# power.net
KiCad netlist of a schematic drawn in Altium Designer
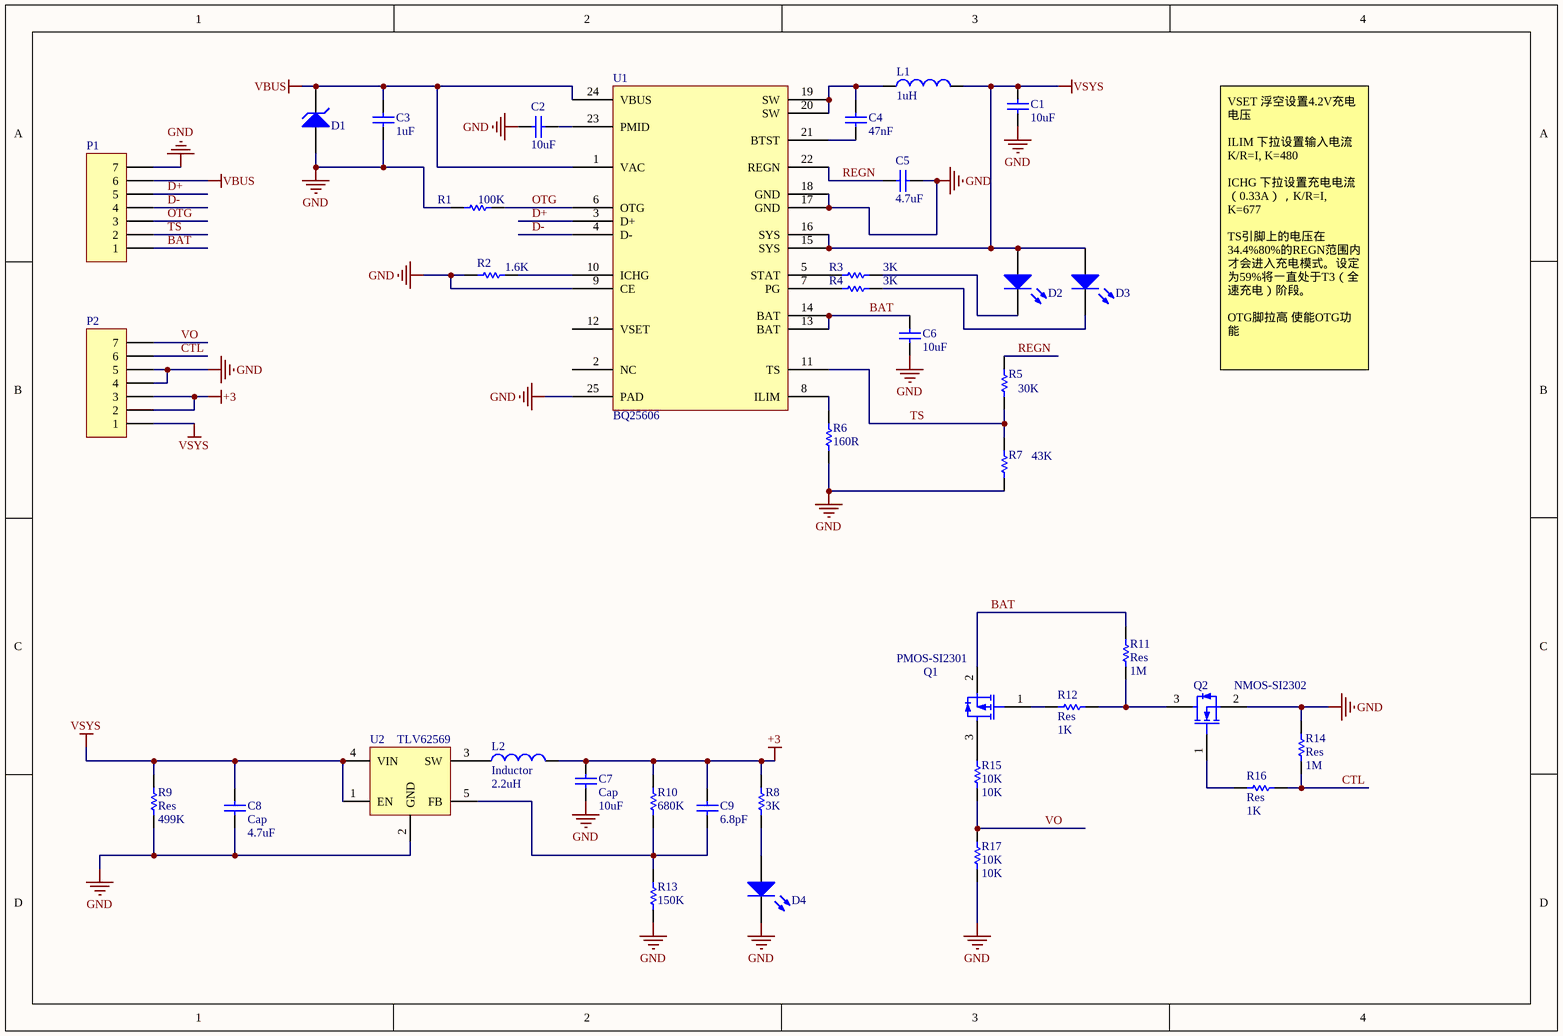
[diagram p0: power.SchDoc]

(export (version "E")
  (design (tool "Eeschema 10.0.6"))
  (components
    (comp (ref "C1")
      (value "10uF")
      (footprint "6-0805_L")
      (description "Capacitor")
      (fields (field (name "PUBLISHER") "Altium Limited"))
      (libsource (lib "Miscellaneous Devices") (part "Cap"))
    )
    (comp (ref "C2")
      (value "10uF")
      (footprint "6-0805_L")
      (description "Capacitor")
      (fields (field (name "PUBLISHER") "Altium Limited"))
      (libsource (lib "Miscellaneous Devices") (part "Cap"))
    )
    (comp (ref "C3")
      (value "1uF")
      (footprint "6-0805_L")
      (description "Capacitor")
      (fields (field (name "PUBLISHER") "Altium Limited"))
      (libsource (lib "Miscellaneous Devices") (part "Cap"))
    )
    (comp (ref "C4")
      (value "47nF")
      (footprint "0402")
      (description "Capacitor")
      (fields (field (name "PUBLISHER") "Altium Limited"))
      (libsource (lib "Miscellaneous Devices") (part "Cap"))
    )
    (comp (ref "C5")
      (value "4.7uF")
      (footprint "6-0805_L")
      (description "Capacitor")
      (fields (field (name "PUBLISHER") "Altium Limited"))
      (libsource (lib "Miscellaneous Devices") (part "Cap"))
    )
    (comp (ref "C6")
      (value "10uF")
      (footprint "6-0805_L")
      (description "Capacitor")
      (fields (field (name "PUBLISHER") "Altium Limited"))
      (libsource (lib "Miscellaneous Devices") (part "Cap"))
    )
    (comp (ref "C7")
      (value "Cap")
      (footprint "6-0805_L")
      (description "Capacitor")
      (fields (field (name "ALTIUM_VALUE") "10uF") (field (name "PUBLISHER") "Altium Limited"))
      (libsource (lib "Miscellaneous Devices") (part "Cap"))
    )
    (comp (ref "C8")
      (value "Cap")
      (footprint "6-0805_L")
      (description "Capacitor")
      (fields (field (name "ALTIUM_VALUE") "4.7uF") (field (name "PUBLISHER") "Altium Limited"))
      (libsource (lib "Miscellaneous Devices") (part "Cap"))
    )
    (comp (ref "C9")
      (value "6.8pF")
      (footprint "0402")
      (description "Capacitor")
      (fields (field (name "PUBLISHER") "Altium Limited"))
      (libsource (lib "Miscellaneous Devices") (part "Cap"))
    )
    (comp (ref "D1") (value "D") (footprint "PESD-SOD323") (libsource (lib "stm32h743") (part "D")))
    (comp (ref "D2") (value "LED RED") (footprint "0402-p") (libsource (lib "stm32h743") (part "LED")))
    (comp (ref "D3") (value "LED") (footprint "0402-p") (libsource (lib "stm32h743") (part "LED")))
    (comp (ref "D4") (value "LED") (footprint "0402-p") (libsource (lib "stm32h743") (part "LED")))
    (comp (ref "L1")
      (value "1uH")
      (footprint "L2520-INDP2520X20L")
      (description "Inductor")
      (fields (field (name "PUBLISHER") "Altium Limited"))
      (libsource (lib "Miscellaneous Devices") (part "Inductor"))
    )
    (comp (ref "L2")
      (value "Inductor")
      (footprint "L2520-INDP2520X20L")
      (fields (field (name "ALTIUM_VALUE") "2.2uH") (field (name "PUBLISHER") "Altium Limited"))
      (libsource (lib "Miscellaneous Devices") (part "Inductor"))
    )
    (comp (ref "P1")
      (value "Header 7")
      (footprint "DIP7-HOLE")
      (description "Header, 7-Pin")
      (fields (field (name "PUBLISHER") "Altium Limited"))
      (libsource (lib "Miscellaneous Connectors") (part "Header 7"))
    )
    (comp (ref "P2")
      (value "Header 7")
      (footprint "DIP7-HOLE")
      (description "Header, 7-Pin")
      (fields (field (name "PUBLISHER") "Altium Limited"))
      (libsource (lib "Miscellaneous Connectors") (part "Header 7"))
    )
    (comp (ref "Q1") (value "PMOS-SI2301") (footprint "SOT23-3") (libsource (lib "stm32h743") (part "PMOS")))
    (comp (ref "Q2") (value "NMOS-SI2302") (footprint "SOT23-3") (libsource (lib "stm32h743") (part "NMOS")))
    (comp (ref "R1")
      (value "100K")
      (footprint "0402")
      (description "Resistor")
      (fields (field (name "PUBLISHER") "Altium Limited"))
      (libsource (lib "Miscellaneous Devices") (part "Res1"))
    )
    (comp (ref "R2")
      (value "1.6K")
      (footprint "0402")
      (description "Resistor")
      (fields (field (name "PUBLISHER") "Altium Limited"))
      (libsource (lib "Miscellaneous Devices") (part "Res1"))
    )
    (comp (ref "R3")
      (value "3K")
      (footprint "0402")
      (description "Resistor")
      (fields (field (name "PUBLISHER") "Altium Limited"))
      (libsource (lib "Miscellaneous Devices") (part "Res1"))
    )
    (comp (ref "R4")
      (value "3K")
      (footprint "0402")
      (description "Resistor")
      (fields (field (name "PUBLISHER") "Altium Limited"))
      (libsource (lib "Miscellaneous Devices") (part "Res1"))
    )
    (comp (ref "R5")
      (value "30K")
      (footprint "0402")
      (description "Resistor")
      (fields (field (name "PUBLISHER") "Altium Limited"))
      (libsource (lib "Miscellaneous Devices") (part "Res1"))
    )
    (comp (ref "R6")
      (value "160R")
      (footprint "0402")
      (description "Resistor")
      (fields (field (name "PUBLISHER") "Altium Limited"))
      (libsource (lib "Miscellaneous Devices") (part "Res1"))
    )
    (comp (ref "R7")
      (value "43K")
      (footprint "0402")
      (description "Resistor")
      (fields (field (name "PUBLISHER") "Altium Limited"))
      (libsource (lib "Miscellaneous Devices") (part "Res1"))
    )
    (comp (ref "R8")
      (value "3K")
      (footprint "0402")
      (description "Resistor")
      (fields (field (name "PUBLISHER") "Altium Limited"))
      (libsource (lib "Miscellaneous Devices") (part "Res1"))
    )
    (comp (ref "R9")
      (value "Res")
      (footprint "0402")
      (description "Resistor")
      (fields (field (name "ALTIUM_VALUE") "499K") (field (name "PUBLISHER") "Altium Limited"))
      (libsource (lib "Miscellaneous Devices") (part "Res1"))
    )
    (comp (ref "R10")
      (value "680K")
      (footprint "0402")
      (description "Resistor")
      (fields (field (name "PUBLISHER") "Altium Limited"))
      (libsource (lib "Miscellaneous Devices") (part "Res1"))
    )
    (comp (ref "R11")
      (value "Res")
      (footprint "0402")
      (description "Resistor")
      (fields (field (name "ALTIUM_VALUE") "1M") (field (name "PUBLISHER") "Altium Limited"))
      (libsource (lib "Miscellaneous Devices") (part "Res1"))
    )
    (comp (ref "R12")
      (value "Res")
      (footprint "0402")
      (description "Resistor")
      (fields (field (name "ALTIUM_VALUE") "1K") (field (name "PUBLISHER") "Altium Limited"))
      (libsource (lib "Miscellaneous Devices") (part "Res1"))
    )
    (comp (ref "R13")
      (value "150K")
      (footprint "0402")
      (description "Resistor")
      (fields (field (name "PUBLISHER") "Altium Limited"))
      (libsource (lib "Miscellaneous Devices") (part "Res1"))
    )
    (comp (ref "R14")
      (value "Res")
      (footprint "0402")
      (description "Resistor")
      (fields (field (name "ALTIUM_VALUE") "1M") (field (name "PUBLISHER") "Altium Limited"))
      (libsource (lib "Miscellaneous Devices") (part "Res1"))
    )
    (comp (ref "R15")
      (value "10K")
      (footprint "0402")
      (description "Resistor")
      (fields (field (name "ALTIUM_VALUE") "10K") (field (name "PUBLISHER") "Altium Limited"))
      (libsource (lib "Miscellaneous Devices") (part "Res1"))
    )
    (comp (ref "R16")
      (value "Res")
      (footprint "0402")
      (description "Resistor")
      (fields (field (name "ALTIUM_VALUE") "1K") (field (name "PUBLISHER") "Altium Limited"))
      (libsource (lib "Miscellaneous Devices") (part "Res1"))
    )
    (comp (ref "R17")
      (value "10K")
      (footprint "0402")
      (description "Resistor")
      (fields (field (name "ALTIUM_VALUE") "10K") (field (name "PUBLISHER") "Altium Limited"))
      (libsource (lib "Miscellaneous Devices") (part "Res1"))
    )
    (comp (ref "U1")
      (value "BQ25606")
      (footprint "QFN24-BQ25606")
      (libsource (lib "stm32h743") (part "BQ25606"))
    )
    (comp (ref "U2") (value "TLV62569") (footprint "SOT23-5") (libsource (lib "stm32h743") (part "TLV62569")))
  )
  (nets
    (net (code "1") (name "+3") (class "Default")
      (node (ref "C7") (pin "2") (pinfunction "2_2") (pintype "passive"))
      (node (ref "C9") (pin "2") (pinfunction "2_2") (pintype "passive"))
      (node (ref "L2") (pin "2") (pinfunction "2_2") (pintype "passive"))
      (node (ref "P2") (pin "2") (pinfunction "2_2") (pintype "passive"))
      (node (ref "P2") (pin "3") (pinfunction "3_3") (pintype "passive"))
      (node (ref "R10") (pin "2") (pinfunction "2_2") (pintype "passive"))
      (node (ref "R8") (pin "2") (pinfunction "2_2") (pintype "passive"))
    )
    (net (code "2") (name "/BAT") (class "Default")
      (node (ref "C6") (pin "1") (pinfunction "1_1") (pintype "passive"))
      (node (ref "P1") (pin "1") (pinfunction "1_1") (pintype "passive"))
      (node (ref "Q1") (pin "2") (pinfunction "S_2") (pintype "passive"))
      (node (ref "R11") (pin "2") (pinfunction "2_2") (pintype "passive"))
      (node (ref "U1") (pin "13") (pinfunction "BAT_13") (pintype "passive"))
      (node (ref "U1") (pin "14") (pinfunction "BAT_14") (pintype "passive"))
    )
    (net (code "3") (name "/CTL") (class "Default")
      (node (ref "P2") (pin "6") (pinfunction "6_6") (pintype "passive"))
      (node (ref "R14") (pin "2") (pinfunction "2_2") (pintype "passive"))
      (node (ref "R16") (pin "2") (pinfunction "2_2") (pintype "passive"))
    )
    (net (code "4") (name "/D+") (class "Default")
      (node (ref "P1") (pin "5") (pinfunction "5_5") (pintype "passive"))
      (node (ref "U1") (pin "3") (pinfunction "D+_3") (pintype "passive"))
    )
    (net (code "5") (name "/D-") (class "Default")
      (node (ref "P1") (pin "4") (pinfunction "4_4") (pintype "passive"))
      (node (ref "U1") (pin "4") (pinfunction "D-_4") (pintype "passive"))
    )
    (net (code "6") (name "/OTG") (class "Default")
      (node (ref "P1") (pin "3") (pinfunction "3_3") (pintype "passive"))
      (node (ref "R1") (pin "1") (pinfunction "1_1") (pintype "passive"))
      (node (ref "U1") (pin "6") (pinfunction "OTG_6") (pintype "passive"))
    )
    (net (code "7") (name "/REGN") (class "Default")
      (node (ref "C5") (pin "1") (pinfunction "1_1") (pintype "passive"))
      (node (ref "R5") (pin "1") (pinfunction "1_1") (pintype "passive"))
      (node (ref "U1") (pin "22") (pinfunction "REGN_22") (pintype "passive"))
    )
    (net (code "8") (name "/TS") (class "Default")
      (node (ref "P1") (pin "2") (pinfunction "2_2") (pintype "passive"))
      (node (ref "R5") (pin "2") (pinfunction "2_2") (pintype "passive"))
      (node (ref "R7") (pin "1") (pinfunction "1_1") (pintype "passive"))
      (node (ref "U1") (pin "11") (pinfunction "TS_11") (pintype "passive"))
    )
    (net (code "9") (name "/VO") (class "Default")
      (node (ref "P2") (pin "7") (pinfunction "7_7") (pintype "passive"))
      (node (ref "R15") (pin "1") (pinfunction "1_1") (pintype "passive"))
      (node (ref "R17") (pin "2") (pinfunction "2_2") (pintype "passive"))
    )
    (net (code "10") (name "GND") (class "Default")
      (node (ref "C1") (pin "2") (pinfunction "2_2") (pintype "passive"))
      (node (ref "C2") (pin "2") (pinfunction "2_2") (pintype "passive"))
      (node (ref "C3") (pin "1") (pinfunction "1_1") (pintype "passive"))
      (node (ref "C5") (pin "2") (pinfunction "2_2") (pintype "passive"))
      (node (ref "C6") (pin "2") (pinfunction "2_2") (pintype "passive"))
      (node (ref "C7") (pin "1") (pinfunction "1_1") (pintype "passive"))
      (node (ref "C8") (pin "1") (pinfunction "1_1") (pintype "passive"))
      (node (ref "D1") (pin "2") (pinfunction "A_2") (pintype "passive"))
      (node (ref "D4") (pin "1") (pinfunction "K_1") (pintype "passive"))
      (node (ref "P1") (pin "7") (pinfunction "7_7") (pintype "passive"))
      (node (ref "P2") (pin "4") (pinfunction "4_4") (pintype "passive"))
      (node (ref "P2") (pin "5") (pinfunction "5_5") (pintype "passive"))
      (node (ref "Q2") (pin "2") (pinfunction "S_2") (pintype "passive"))
      (node (ref "R1") (pin "2") (pinfunction "2_2") (pintype "passive"))
      (node (ref "R13") (pin "1") (pinfunction "1_1") (pintype "passive"))
      (node (ref "R14") (pin "1") (pinfunction "1_1") (pintype "passive"))
      (node (ref "R17") (pin "1") (pinfunction "1_1") (pintype "passive"))
      (node (ref "R2") (pin "2") (pinfunction "2_2") (pintype "passive"))
      (node (ref "R6") (pin "1") (pinfunction "1_1") (pintype "passive"))
      (node (ref "R7") (pin "2") (pinfunction "2_2") (pintype "passive"))
      (node (ref "R9") (pin "1") (pinfunction "1_1") (pintype "passive"))
      (node (ref "U1") (pin "17") (pinfunction "GND_17") (pintype "passive"))
      (node (ref "U1") (pin "18") (pinfunction "GND_18") (pintype "passive"))
      (node (ref "U1") (pin "25") (pinfunction "PAD_25") (pintype "passive"))
      (node (ref "U1") (pin "9") (pinfunction "CE_9") (pintype "passive"))
      (node (ref "U2") (pin "2") (pinfunction "GND_2") (pintype "passive"))
    )
    (net (code "11") (name "Net-(C4-Pad2)") (class "Default")
      (node (ref "C4") (pin "2") (pinfunction "2_2") (pintype "passive"))
      (node (ref "L1") (pin "1") (pinfunction "1_1") (pintype "passive"))
      (node (ref "U1") (pin "19") (pinfunction "SW_19") (pintype "passive"))
      (node (ref "U1") (pin "20") (pinfunction "SW_20") (pintype "passive"))
    )
    (net (code "12") (name "Net-(D2-K)") (class "Default")
      (node (ref "D2") (pin "1") (pinfunction "K_1") (pintype "passive"))
      (node (ref "R3") (pin "1") (pinfunction "1_1") (pintype "passive"))
    )
    (net (code "13") (name "Net-(D3-K)") (class "Default")
      (node (ref "D3") (pin "1") (pinfunction "K_1") (pintype "passive"))
      (node (ref "R4") (pin "1") (pinfunction "1_1") (pintype "passive"))
    )
    (net (code "14") (name "Net-(D4-A)") (class "Default")
      (node (ref "D4") (pin "2") (pinfunction "A_2") (pintype "passive"))
      (node (ref "R8") (pin "1") (pinfunction "1_1") (pintype "passive"))
    )
    (net (code "15") (name "Net-(Q1-D)") (class "Default")
      (node (ref "Q1") (pin "3") (pinfunction "D_3") (pintype "passive"))
      (node (ref "R15") (pin "2") (pinfunction "2_2") (pintype "passive"))
    )
    (net (code "16") (name "Net-(Q1-G)") (class "Default")
      (node (ref "Q1") (pin "1") (pinfunction "G_1") (pintype "passive"))
      (node (ref "R12") (pin "2") (pinfunction "2_2") (pintype "passive"))
    )
    (net (code "17") (name "Net-(Q2-D)") (class "Default")
      (node (ref "Q2") (pin "3") (pinfunction "D_3") (pintype "passive"))
      (node (ref "R11") (pin "1") (pinfunction "1_1") (pintype "passive"))
      (node (ref "R12") (pin "1") (pinfunction "1_1") (pintype "passive"))
    )
    (net (code "18") (name "Net-(Q2-G)") (class "Default")
      (node (ref "Q2") (pin "1") (pinfunction "G_1") (pintype "passive"))
      (node (ref "R16") (pin "1") (pinfunction "1_1") (pintype "passive"))
    )
    (net (code "19") (name "Net-(U1-BTST)") (class "Default")
      (node (ref "C4") (pin "1") (pinfunction "1_1") (pintype "passive"))
      (node (ref "U1") (pin "21") (pinfunction "BTST_21") (pintype "passive"))
    )
    (net (code "20") (name "Net-(U1-ICHG)") (class "Default")
      (node (ref "R2") (pin "1") (pinfunction "1_1") (pintype "passive"))
      (node (ref "U1") (pin "10") (pinfunction "ICHG_10") (pintype "passive"))
    )
    (net (code "21") (name "Net-(U1-ILIM)") (class "Default")
      (node (ref "R6") (pin "2") (pinfunction "2_2") (pintype "passive"))
      (node (ref "U1") (pin "8") (pinfunction "ILIM_8") (pintype "passive"))
    )
    (net (code "22") (name "Net-(U1-PG)") (class "Default")
      (node (ref "R4") (pin "2") (pinfunction "2_2") (pintype "passive"))
      (node (ref "U1") (pin "7") (pinfunction "PG_7") (pintype "passive"))
    )
    (net (code "23") (name "Net-(U1-PMID)") (class "Default")
      (node (ref "C2") (pin "1") (pinfunction "1_1") (pintype "passive"))
      (node (ref "U1") (pin "23") (pinfunction "PMID_23") (pintype "passive"))
    )
    (net (code "24") (name "Net-(U1-STAT)") (class "Default")
      (node (ref "R3") (pin "2") (pinfunction "2_2") (pintype "passive"))
      (node (ref "U1") (pin "5") (pinfunction "STAT_5") (pintype "passive"))
    )
    (net (code "25") (name "Net-(U2-FB)") (class "Default")
      (node (ref "C9") (pin "1") (pinfunction "1_1") (pintype "passive"))
      (node (ref "R10") (pin "1") (pinfunction "1_1") (pintype "passive"))
      (node (ref "R13") (pin "2") (pinfunction "2_2") (pintype "passive"))
      (node (ref "U2") (pin "5") (pinfunction "FB_5") (pintype "passive"))
    )
    (net (code "26") (name "Net-(U2-SW)") (class "Default")
      (node (ref "L2") (pin "1") (pinfunction "1_1") (pintype "passive"))
      (node (ref "U2") (pin "3") (pinfunction "SW_3") (pintype "passive"))
    )
    (net (code "27") (name "VBUS") (class "Default")
      (node (ref "C3") (pin "2") (pinfunction "2_2") (pintype "passive"))
      (node (ref "D1") (pin "1") (pinfunction "K_1") (pintype "passive"))
      (node (ref "P1") (pin "6") (pinfunction "6_6") (pintype "passive"))
      (node (ref "U1") (pin "1") (pinfunction "VAC_1") (pintype "passive"))
      (node (ref "U1") (pin "24") (pinfunction "VBUS_24") (pintype "passive"))
    )
    (net (code "28") (name "VSYS") (class "Default")
      (node (ref "C1") (pin "1") (pinfunction "1_1") (pintype "passive"))
      (node (ref "C8") (pin "2") (pinfunction "2_2") (pintype "passive"))
      (node (ref "D2") (pin "2") (pinfunction "A_2") (pintype "passive"))
      (node (ref "D3") (pin "2") (pinfunction "A_2") (pintype "passive"))
      (node (ref "L1") (pin "2") (pinfunction "2_2") (pintype "passive"))
      (node (ref "P2") (pin "1") (pinfunction "1_1") (pintype "passive"))
      (node (ref "R9") (pin "2") (pinfunction "2_2") (pintype "passive"))
      (node (ref "U1") (pin "15") (pinfunction "SYS_15") (pintype "passive"))
      (node (ref "U1") (pin "16") (pinfunction "SYS_16") (pintype "passive"))
      (node (ref "U2") (pin "1") (pinfunction "EN_1") (pintype "passive"))
      (node (ref "U2") (pin "4") (pinfunction "VIN_4") (pintype "passive"))
    )
    (net (code "29") (name "unconnected-(U1-NC-Pad2)") (class "Default")
      (node (ref "U1") (pin "2") (pinfunction "NC_2") (pintype "passive"))
    )
    (net (code "30") (name "unconnected-(U1-VSET-Pad12)") (class "Default")
      (node (ref "U1") (pin "12") (pinfunction "VSET_12") (pintype "passive"))
    )
  )
)
